# LinuxBoard_v1_4.net
KiCad netlist of a schematic drawn in EAGLE
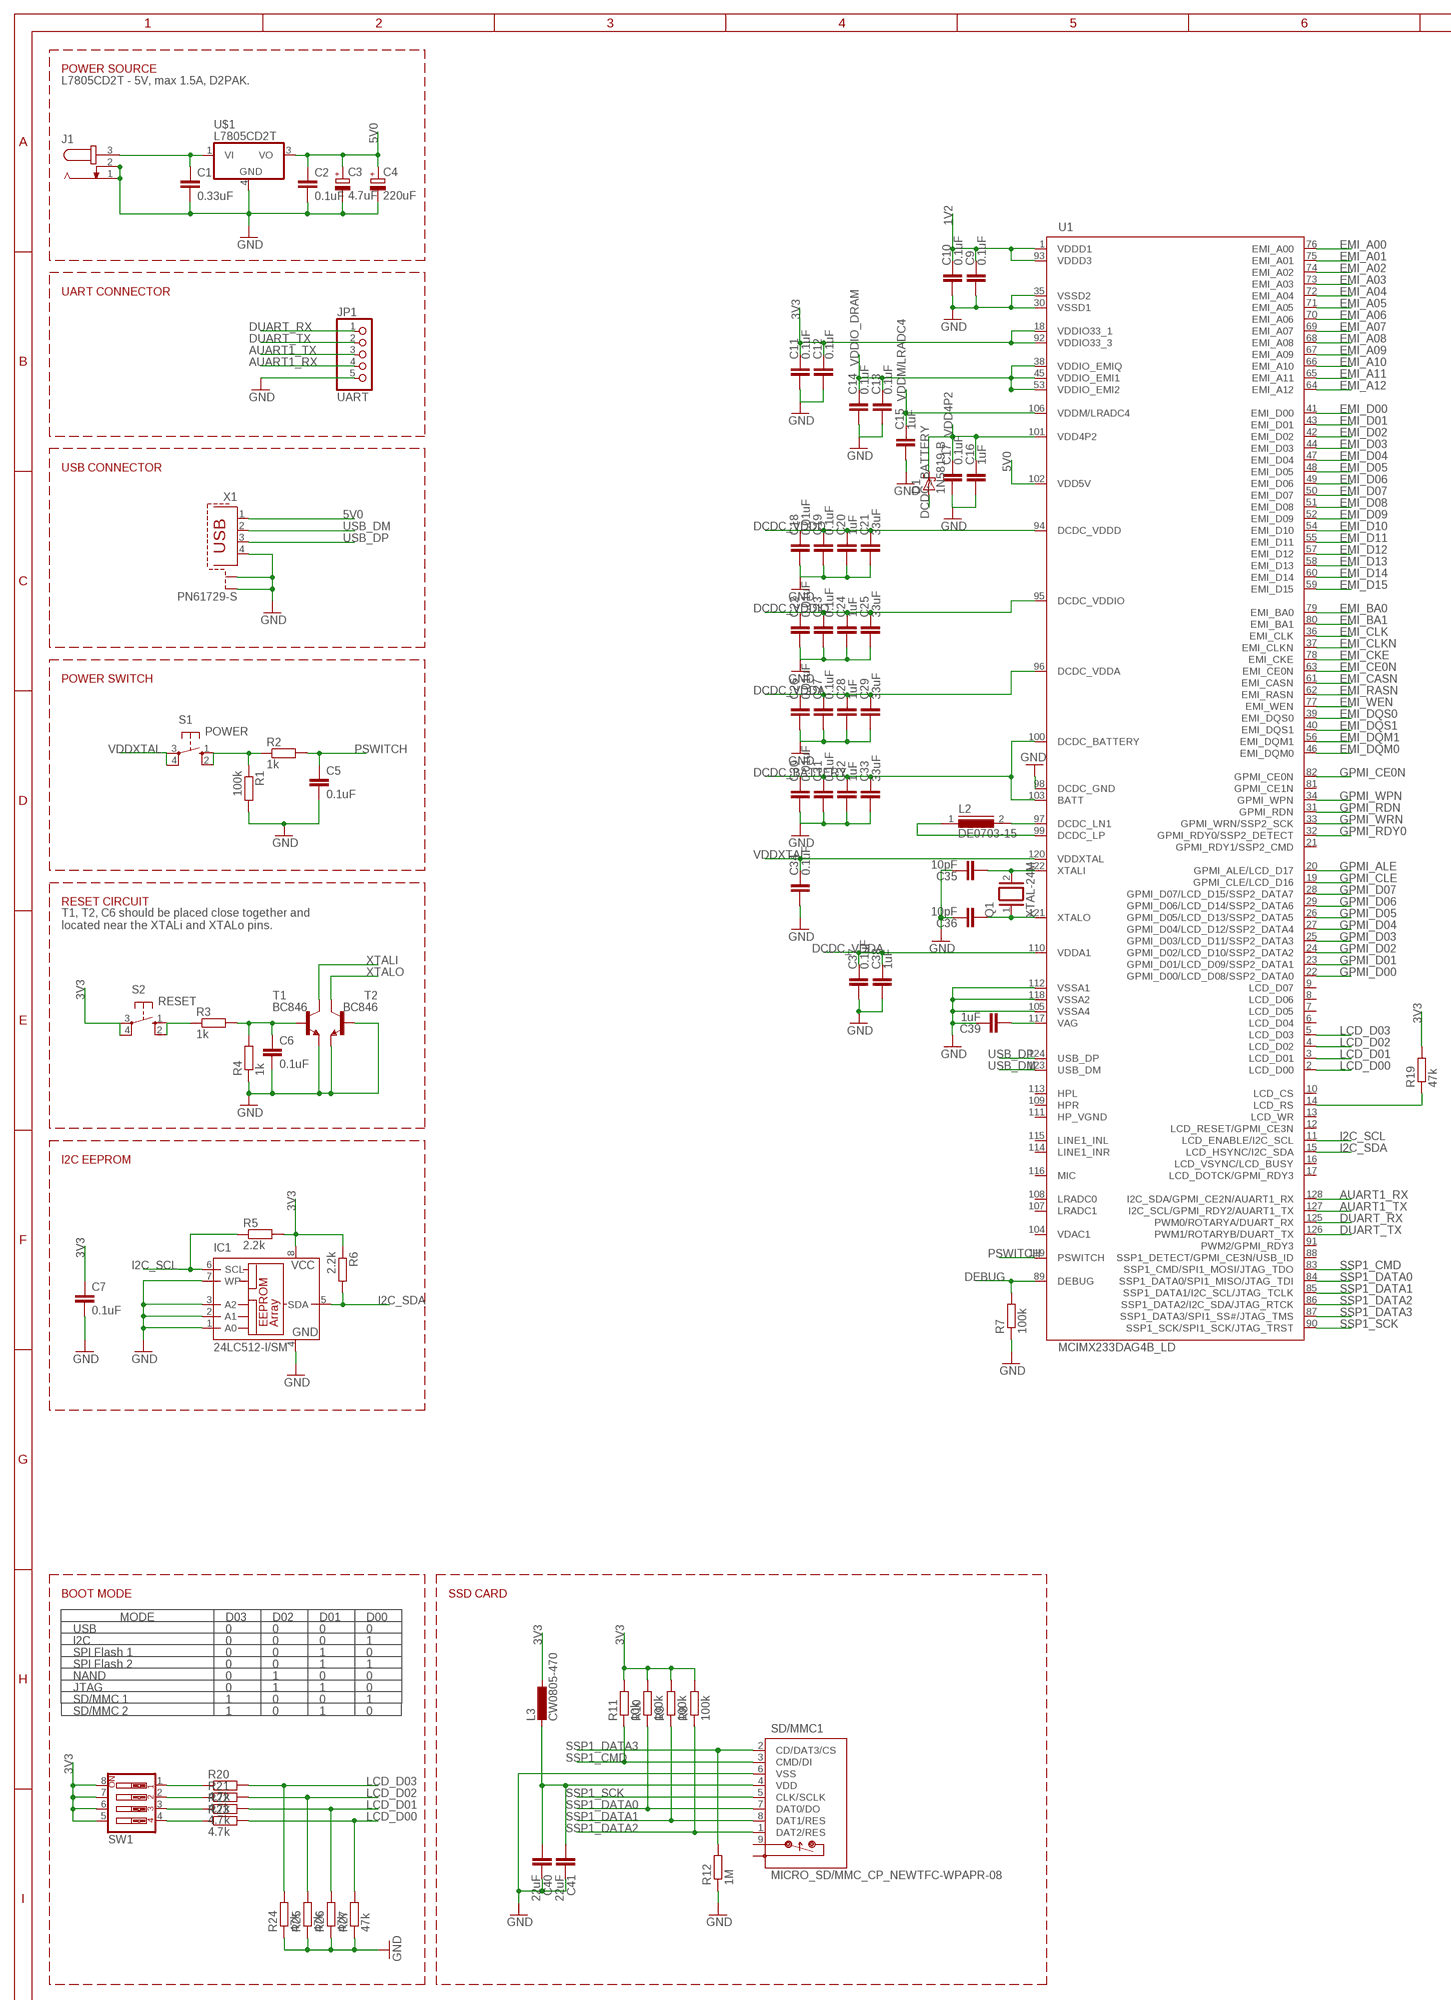
[diagram p0: schematic, sheet 1, part 1 of 2]
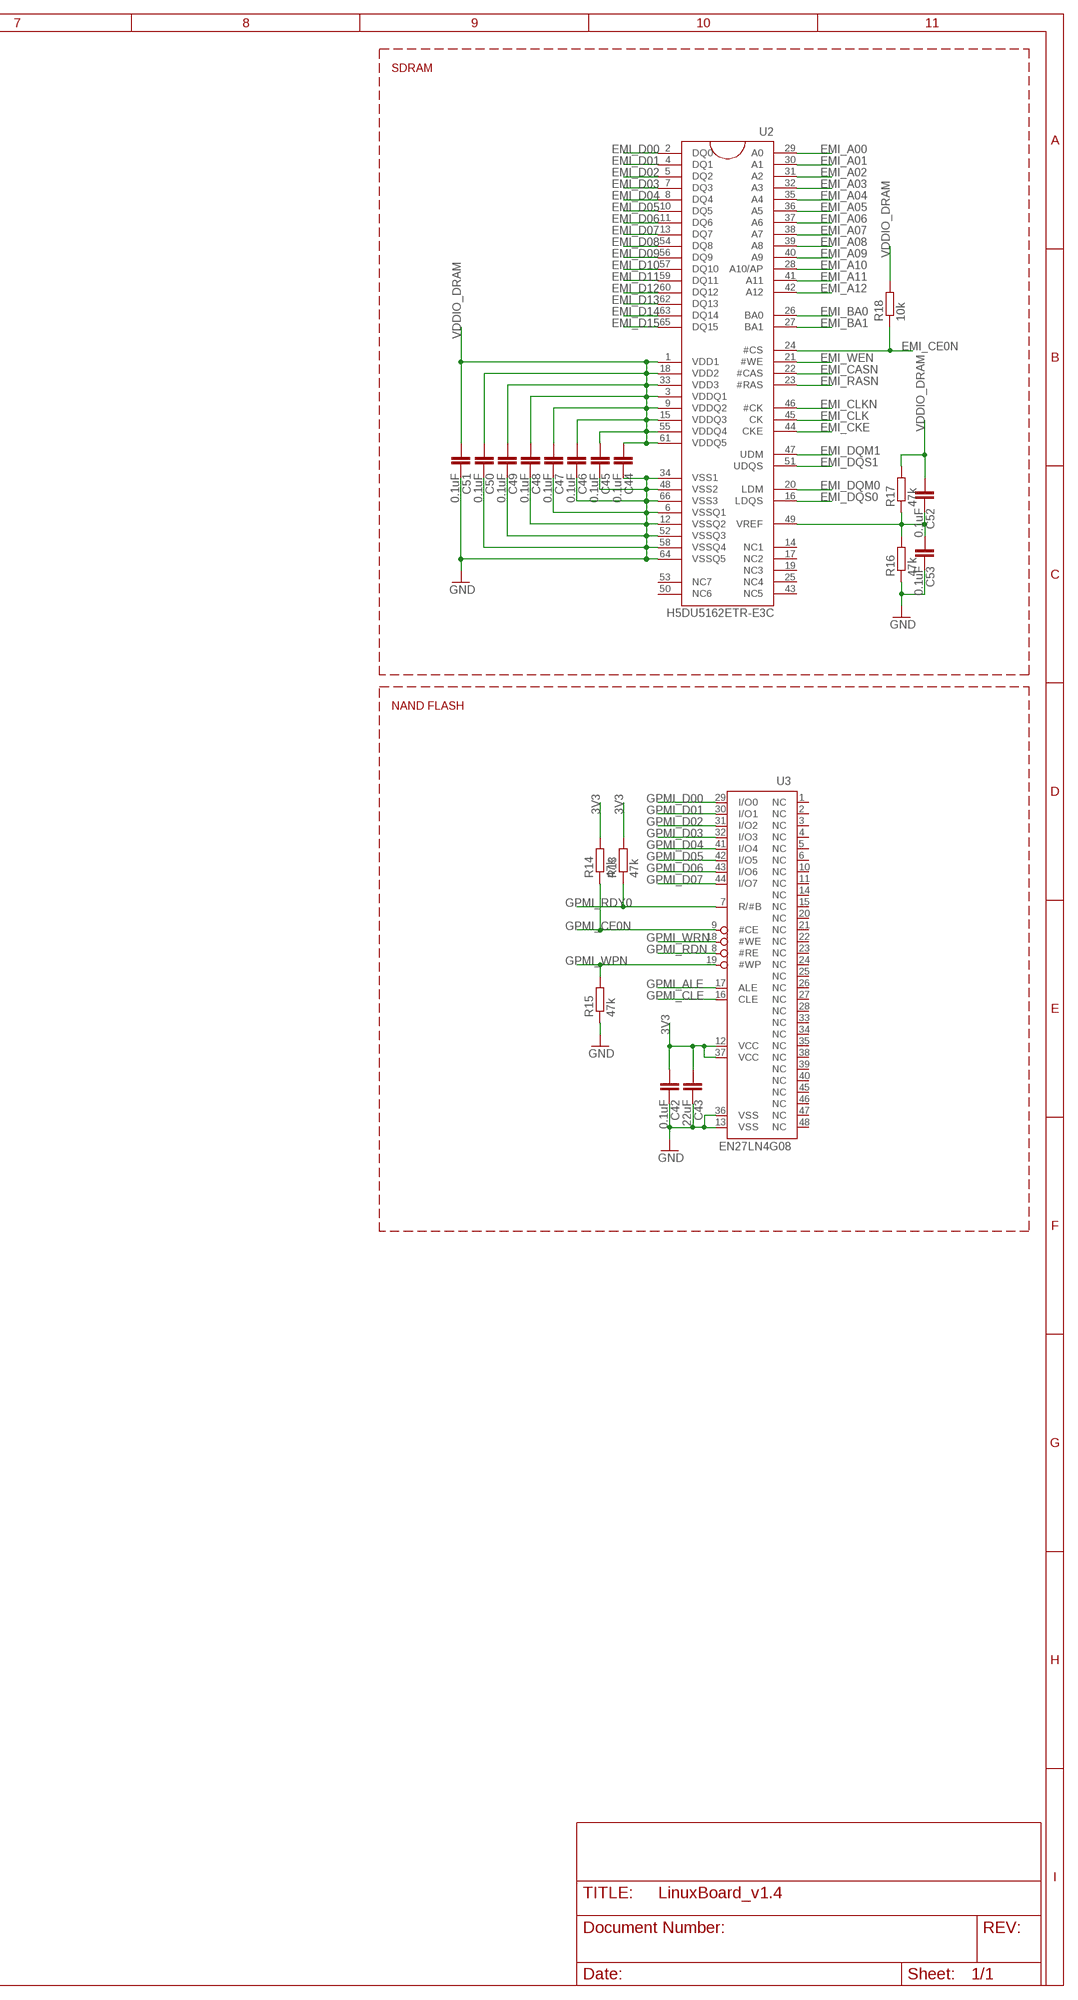
[diagram p1: schematic, sheet 1, part 2 of 2]

(export (version "E")
  (design (tool "Eeschema 10.0.6"))
  (components
    (comp (ref "C1")
      (value "0.33uF")
      (footprint "eagle-import:C0805")
      (libsource (lib "eagle-import") (part "C-EUC0805"))
    )
    (comp (ref "C2")
      (value "0.1uF")
      (footprint "eagle-import:C0805")
      (libsource (lib "eagle-import") (part "C-EUC0805"))
    )
    (comp (ref "C3")
      (value "4.7uF")
      (footprint "eagle-import:E2-5")
      (libsource (lib "eagle-import") (part "CPOL-EUE2-5"))
    )
    (comp (ref "C4")
      (value "220uF")
      (footprint "eagle-import:E2-5")
      (libsource (lib "eagle-import") (part "CPOL-EUE2-5"))
    )
    (comp (ref "C5")
      (value "0.1uF")
      (footprint "eagle-import:C0805")
      (libsource (lib "eagle-import") (part "C-EUC0805"))
    )
    (comp (ref "C6")
      (value "0.1uF")
      (footprint "eagle-import:C0805")
      (libsource (lib "eagle-import") (part "C-EUC0805"))
    )
    (comp (ref "C7")
      (value "0.1uF")
      (footprint "eagle-import:C0805")
      (libsource (lib "eagle-import") (part "C-EUC0805"))
    )
    (comp (ref "C9")
      (value "0.1uF")
      (footprint "eagle-import:C0805")
      (libsource (lib "eagle-import") (part "C-EUC0805"))
    )
    (comp (ref "C10")
      (value "0.1uF")
      (footprint "eagle-import:C0805")
      (libsource (lib "eagle-import") (part "C-EUC0805"))
    )
    (comp (ref "C11")
      (value "0.1uF")
      (footprint "eagle-import:C0805")
      (libsource (lib "eagle-import") (part "C-EUC0805"))
    )
    (comp (ref "C12")
      (value "0.1uF")
      (footprint "eagle-import:C0805")
      (libsource (lib "eagle-import") (part "C-EUC0805"))
    )
    (comp (ref "C13")
      (value "0.1uF")
      (footprint "eagle-import:C0805")
      (libsource (lib "eagle-import") (part "C-EUC0805"))
    )
    (comp (ref "C14")
      (value "0.1uF")
      (footprint "eagle-import:C0805")
      (libsource (lib "eagle-import") (part "C-EUC0805"))
    )
    (comp (ref "C15")
      (value "1uF")
      (footprint "eagle-import:C0805")
      (libsource (lib "eagle-import") (part "C-EUC0805"))
    )
    (comp (ref "C16")
      (value "1uF")
      (footprint "eagle-import:C0805")
      (libsource (lib "eagle-import") (part "C-EUC0805"))
    )
    (comp (ref "C17")
      (value "0.1uF")
      (footprint "eagle-import:C0805")
      (libsource (lib "eagle-import") (part "C-EUC0805"))
    )
    (comp (ref "C18")
      (value "0.01uF")
      (footprint "eagle-import:C0805")
      (libsource (lib "eagle-import") (part "C-EUC0805"))
    )
    (comp (ref "C19")
      (value "0.1uF")
      (footprint "eagle-import:C0805")
      (libsource (lib "eagle-import") (part "C-EUC0805"))
    )
    (comp (ref "C20")
      (value "1uF")
      (footprint "eagle-import:C0805")
      (libsource (lib "eagle-import") (part "C-EUC0805"))
    )
    (comp (ref "C21")
      (value "33uF")
      (footprint "eagle-import:C0805")
      (libsource (lib "eagle-import") (part "C-EUC0805"))
    )
    (comp (ref "C22")
      (value "0.01uF")
      (footprint "eagle-import:C0805")
      (libsource (lib "eagle-import") (part "C-EUC0805"))
    )
    (comp (ref "C23")
      (value "0.1uF")
      (footprint "eagle-import:C0805")
      (libsource (lib "eagle-import") (part "C-EUC0805"))
    )
    (comp (ref "C24")
      (value "1uF")
      (footprint "eagle-import:C0805")
      (libsource (lib "eagle-import") (part "C-EUC0805"))
    )
    (comp (ref "C25")
      (value "33uF")
      (footprint "eagle-import:C0805")
      (libsource (lib "eagle-import") (part "C-EUC0805"))
    )
    (comp (ref "C26")
      (value "0.01uF")
      (footprint "eagle-import:C0805")
      (libsource (lib "eagle-import") (part "C-EUC0805"))
    )
    (comp (ref "C27")
      (value "0.1uF")
      (footprint "eagle-import:C0805")
      (libsource (lib "eagle-import") (part "C-EUC0805"))
    )
    (comp (ref "C28")
      (value "1uF")
      (footprint "eagle-import:C0805")
      (libsource (lib "eagle-import") (part "C-EUC0805"))
    )
    (comp (ref "C29")
      (value "33uF")
      (footprint "eagle-import:C0805")
      (libsource (lib "eagle-import") (part "C-EUC0805"))
    )
    (comp (ref "C30")
      (value "0.01uF")
      (footprint "eagle-import:C0805")
      (libsource (lib "eagle-import") (part "C-EUC0805"))
    )
    (comp (ref "C31")
      (value "0.1uF")
      (footprint "eagle-import:C0805")
      (libsource (lib "eagle-import") (part "C-EUC0805"))
    )
    (comp (ref "C32")
      (value "1uF")
      (footprint "eagle-import:C0805")
      (libsource (lib "eagle-import") (part "C-EUC0805"))
    )
    (comp (ref "C33")
      (value "33uF")
      (footprint "eagle-import:C0805")
      (libsource (lib "eagle-import") (part "C-EUC0805"))
    )
    (comp (ref "C34")
      (value "0.1uF")
      (footprint "eagle-import:C0805")
      (libsource (lib "eagle-import") (part "C-EUC0805"))
    )
    (comp (ref "C35")
      (value "10pF")
      (footprint "eagle-import:C0805")
      (libsource (lib "eagle-import") (part "C-EUC0805"))
    )
    (comp (ref "C36")
      (value "10pF")
      (footprint "eagle-import:C0805")
      (libsource (lib "eagle-import") (part "C-EUC0805"))
    )
    (comp (ref "C37")
      (value "0.1uF")
      (footprint "eagle-import:C0805")
      (libsource (lib "eagle-import") (part "C-EUC0805"))
    )
    (comp (ref "C38")
      (value "1uF")
      (footprint "eagle-import:C0805")
      (libsource (lib "eagle-import") (part "C-EUC0805"))
    )
    (comp (ref "C39")
      (value "1uF")
      (footprint "eagle-import:C0805")
      (libsource (lib "eagle-import") (part "C-EUC0805"))
    )
    (comp (ref "C40")
      (value "22uF")
      (footprint "eagle-import:C0805")
      (libsource (lib "eagle-import") (part "C-EUC0805"))
    )
    (comp (ref "C41")
      (value "22uF")
      (footprint "eagle-import:C0805")
      (libsource (lib "eagle-import") (part "C-EUC0805"))
    )
    (comp (ref "C42")
      (value "0.1uF")
      (footprint "eagle-import:C0805")
      (libsource (lib "eagle-import") (part "C-EUC0805"))
    )
    (comp (ref "C43")
      (value "22uF")
      (footprint "eagle-import:C0805")
      (libsource (lib "eagle-import") (part "C-EUC0805"))
    )
    (comp (ref "C44")
      (value "0.1uF")
      (footprint "eagle-import:C0805")
      (libsource (lib "eagle-import") (part "C-EUC0805"))
    )
    (comp (ref "C45")
      (value "0.1uF")
      (footprint "eagle-import:C0805")
      (libsource (lib "eagle-import") (part "C-EUC0805"))
    )
    (comp (ref "C46")
      (value "0.1uF")
      (footprint "eagle-import:C0805")
      (libsource (lib "eagle-import") (part "C-EUC0805"))
    )
    (comp (ref "C47")
      (value "0.1uF")
      (footprint "eagle-import:C0805")
      (libsource (lib "eagle-import") (part "C-EUC0805"))
    )
    (comp (ref "C48")
      (value "0.1uF")
      (footprint "eagle-import:C0805")
      (libsource (lib "eagle-import") (part "C-EUC0805"))
    )
    (comp (ref "C49")
      (value "0.1uF")
      (footprint "eagle-import:C0805")
      (libsource (lib "eagle-import") (part "C-EUC0805"))
    )
    (comp (ref "C50")
      (value "0.1uF")
      (footprint "eagle-import:C0805")
      (libsource (lib "eagle-import") (part "C-EUC0805"))
    )
    (comp (ref "C51")
      (value "0.1uF")
      (footprint "eagle-import:C0805")
      (libsource (lib "eagle-import") (part "C-EUC0805"))
    )
    (comp (ref "C52")
      (value "0.1uF")
      (footprint "eagle-import:C0805")
      (libsource (lib "eagle-import") (part "C-EUC0805"))
    )
    (comp (ref "C53")
      (value "0.1uF")
      (footprint "eagle-import:C0805")
      (libsource (lib "eagle-import") (part "C-EUC0805"))
    )
    (comp (ref "D1")
      (value "1N5819-B")
      (footprint "eagle-import:DO41-7.6")
      (libsource (lib "eagle-import") (part "1N5819-B"))
    )
    (comp (ref "IC1")
      (value "24LC512-I/SM")
      (footprint "eagle-import:SO-08")
      (fields (field (name "MF") "MICROCHIP") (field (name "MPN") "24LC128-I/SNG"))
      (libsource (lib "eagle-import") (part "24SNLC128"))
    )
    (comp (ref "J1")
      (value "JACK-PLUG0")
      (footprint "eagle-import:SPC4077")
      (libsource (lib "eagle-import") (part "JACK-PLUG0"))
    )
    (comp (ref "JP1")
      (value "UART")
      (footprint "eagle-import:1X05")
      (libsource (lib "eagle-import") (part "PINHD-1X5"))
    )
    (comp (ref "L2")
      (value "DE0703-15")
      (footprint "eagle-import:DR73")
      (libsource (lib "eagle-import") (part "DR73"))
    )
    (comp (ref "L3")
      (value "CW0805-470")
      (footprint "eagle-import:L2012C")
      (libsource (lib "eagle-import") (part "L-EUL2012C"))
    )
    (comp (ref "Q1")
      (value "XTAL-24M")
      (footprint "eagle-import:QS")
      (libsource (lib "eagle-import") (part "XTAL/S"))
    )
    (comp (ref "R1")
      (value "100k")
      (footprint "eagle-import:R0805")
      (libsource (lib "eagle-import") (part "R-EU_R0805"))
    )
    (comp (ref "R2")
      (value "1k")
      (footprint "eagle-import:R0805")
      (libsource (lib "eagle-import") (part "R-EU_R0805"))
    )
    (comp (ref "R3")
      (value "1k")
      (footprint "eagle-import:R0805")
      (libsource (lib "eagle-import") (part "R-EU_R0805"))
    )
    (comp (ref "R4")
      (value "1k")
      (footprint "eagle-import:R0805")
      (libsource (lib "eagle-import") (part "R-EU_R0805"))
    )
    (comp (ref "R5")
      (value "2.2k")
      (footprint "eagle-import:R0805")
      (libsource (lib "eagle-import") (part "R-EU_R0805"))
    )
    (comp (ref "R6")
      (value "2.2k")
      (footprint "eagle-import:R0805")
      (libsource (lib "eagle-import") (part "R-EU_R0805"))
    )
    (comp (ref "R7")
      (value "100k")
      (footprint "eagle-import:R0805")
      (libsource (lib "eagle-import") (part "R-EU_R0805"))
    )
    (comp (ref "R8")
      (value "100k")
      (footprint "eagle-import:R0805")
      (libsource (lib "eagle-import") (part "R-EU_R0805"))
    )
    (comp (ref "R9")
      (value "100k")
      (footprint "eagle-import:R0805")
      (libsource (lib "eagle-import") (part "R-EU_R0805"))
    )
    (comp (ref "R10")
      (value "100k")
      (footprint "eagle-import:R0805")
      (libsource (lib "eagle-import") (part "R-EU_R0805"))
    )
    (comp (ref "R11")
      (value "10k")
      (footprint "eagle-import:R0805")
      (libsource (lib "eagle-import") (part "R-EU_R0805"))
    )
    (comp (ref "R12")
      (value "1M")
      (footprint "eagle-import:R0805")
      (libsource (lib "eagle-import") (part "R-EU_R0805"))
    )
    (comp (ref "R13")
      (value "47k")
      (footprint "eagle-import:R0805")
      (libsource (lib "eagle-import") (part "R-EU_R0805"))
    )
    (comp (ref "R14")
      (value "47k")
      (footprint "eagle-import:R0805")
      (libsource (lib "eagle-import") (part "R-EU_R0805"))
    )
    (comp (ref "R15")
      (value "47k")
      (footprint "eagle-import:R0805")
      (libsource (lib "eagle-import") (part "R-EU_R0805"))
    )
    (comp (ref "R16")
      (value "47k")
      (footprint "eagle-import:R0805")
      (libsource (lib "eagle-import") (part "R-EU_R0805"))
    )
    (comp (ref "R17")
      (value "47k")
      (footprint "eagle-import:R0805")
      (libsource (lib "eagle-import") (part "R-EU_R0805"))
    )
    (comp (ref "R18")
      (value "10k")
      (footprint "eagle-import:R0805")
      (libsource (lib "eagle-import") (part "R-EU_R0805"))
    )
    (comp (ref "R19")
      (value "47k")
      (footprint "eagle-import:R0805")
      (libsource (lib "eagle-import") (part "R-EU_R0805"))
    )
    (comp (ref "R20")
      (value "4.7k")
      (footprint "eagle-import:R0805")
      (libsource (lib "eagle-import") (part "R-EU_R0805"))
    )
    (comp (ref "R21")
      (value "4.7k")
      (footprint "eagle-import:R0805")
      (libsource (lib "eagle-import") (part "R-EU_R0805"))
    )
    (comp (ref "R22")
      (value "4.7k")
      (footprint "eagle-import:R0805")
      (libsource (lib "eagle-import") (part "R-EU_R0805"))
    )
    (comp (ref "R23")
      (value "4.7k")
      (footprint "eagle-import:R0805")
      (libsource (lib "eagle-import") (part "R-EU_R0805"))
    )
    (comp (ref "R24")
      (value "47k")
      (footprint "eagle-import:R0805")
      (libsource (lib "eagle-import") (part "R-EU_R0805"))
    )
    (comp (ref "R25")
      (value "47k")
      (footprint "eagle-import:R0805")
      (libsource (lib "eagle-import") (part "R-EU_R0805"))
    )
    (comp (ref "R26")
      (value "47k")
      (footprint "eagle-import:R0805")
      (libsource (lib "eagle-import") (part "R-EU_R0805"))
    )
    (comp (ref "R27")
      (value "47k")
      (footprint "eagle-import:R0805")
      (libsource (lib "eagle-import") (part "R-EU_R0805"))
    )
    (comp (ref "S1")
      (value "POWER")
      (footprint "eagle-import:B3F-10XX")
      (fields (field (name "MPN") "B3F-1000"))
      (libsource (lib "eagle-import") (part "10-XX"))
    )
    (comp (ref "S2")
      (value "RESET")
      (footprint "eagle-import:B3F-10XX")
      (fields (field (name "MPN") "B3F-1000"))
      (libsource (lib "eagle-import") (part "10-XX"))
    )
    (comp (ref "SD/MMC1")
      (value "MICRO_SD/MMC_CP_NEWTFC-WPAPR-08")
      (footprint "eagle-import:TFC-WPAPR-08")
      (libsource (lib "eagle-import") (part "MICRO_SD/MMC_CP_NEWTFC-WPAPR-08"))
    )
    (comp (ref "SW1")
      (value "SW_DIP-4")
      (footprint "eagle-import:EDG-04")
      (libsource (lib "eagle-import") (part "SW_DIP-4"))
    )
    (comp (ref "T1")
      (value "BC846")
      (footprint "eagle-import:SOT23")
      (libsource (lib "eagle-import") (part "BC846"))
    )
    (comp (ref "T2")
      (value "BC846")
      (footprint "eagle-import:SOT23")
      (libsource (lib "eagle-import") (part "BC846"))
    )
    (comp (ref "U$1")
      (value "L7805CD2T")
      (footprint "eagle-import:D2PAK-3")
      (libsource (lib "eagle-import") (part "L7805CD2T"))
    )
    (comp (ref "U1")
      (value "MCIMX233DAG4B_LD")
      (footprint "eagle-import:TQFP128LD")
      (libsource (lib "eagle-import") (part "MCIMX233DAG4B_LD"))
    )
    (comp (ref "U2")
      (value "H5DU5162ETR-E3C")
      (footprint "eagle-import:66TSOP-II")
      (libsource (lib "eagle-import") (part "HY5DU121622D(L)T(P)-J"))
    )
    (comp (ref "U3")
      (value "EN27LN4G08")
      (footprint "eagle-import:TSOP48")
      (libsource (lib "eagle-import") (part "H27UBG8T2A"))
    )
    (comp (ref "X1")
      (value "PN61729-S")
      (footprint "eagle-import:PN61729-S")
      (libsource (lib "eagle-import") (part "PN61729-S"))
    )
  )
  (nets
    (net (code "1") (name "/1V2") (class "Default")
      (node (ref "C10") (pin "1") (pinfunction "1_1") (pintype "passive"))
      (node (ref "C9") (pin "1") (pinfunction "1_1") (pintype "passive"))
      (node (ref "U1") (pin "1") (pinfunction "VDDD1_1") (pintype "power_in"))
      (node (ref "U1") (pin "93") (pinfunction "VDDD3_93") (pintype "power_in"))
    )
    (net (code "2") (name "/3V3") (class "Default")
      (node (ref "C11") (pin "1") (pinfunction "1_1") (pintype "passive"))
      (node (ref "C12") (pin "1") (pinfunction "1_1") (pintype "passive"))
      (node (ref "C42") (pin "2") (pinfunction "2_2") (pintype "passive"))
      (node (ref "C43") (pin "2") (pinfunction "2_2") (pintype "passive"))
      (node (ref "C7") (pin "1") (pinfunction "1_1") (pintype "passive"))
      (node (ref "IC1") (pin "8") (pinfunction "VCC_8") (pintype "power_in"))
      (node (ref "L3") (pin "1") (pinfunction "1_1") (pintype "passive"))
      (node (ref "R10") (pin "2") (pinfunction "2_2") (pintype "passive"))
      (node (ref "R11") (pin "2") (pinfunction "2_2") (pintype "passive"))
      (node (ref "R13") (pin "2") (pinfunction "2_2") (pintype "passive"))
      (node (ref "R14") (pin "2") (pinfunction "2_2") (pintype "passive"))
      (node (ref "R19") (pin "2") (pinfunction "2_2") (pintype "passive"))
      (node (ref "R5") (pin "2") (pinfunction "2_2") (pintype "passive"))
      (node (ref "R6") (pin "1") (pinfunction "1_1") (pintype "passive"))
      (node (ref "R8") (pin "2") (pinfunction "2_2") (pintype "passive"))
      (node (ref "R9") (pin "2") (pinfunction "2_2") (pintype "passive"))
      (node (ref "S2") (pin "3") (pinfunction "P_3") (pintype "passive"))
      (node (ref "S2") (pin "4") (pinfunction "P1_4") (pintype "passive"))
      (node (ref "SW1") (pin "5") (pinfunction "5_5") (pintype "passive"))
      (node (ref "SW1") (pin "6") (pinfunction "6_6") (pintype "passive"))
      (node (ref "SW1") (pin "7") (pinfunction "7_7") (pintype "passive"))
      (node (ref "SW1") (pin "8") (pinfunction "8_8") (pintype "passive"))
      (node (ref "U1") (pin "18") (pinfunction "VDDIO33_1_18") (pintype "power_in"))
      (node (ref "U1") (pin "92") (pinfunction "VDDIO33_3_92") (pintype "power_in"))
      (node (ref "U3") (pin "12") (pinfunction "VCC_12") (pintype "power_in"))
      (node (ref "U3") (pin "37") (pinfunction "VCC_37") (pintype "power_in"))
    )
    (net (code "3") (name "/5V0") (class "Default")
      (node (ref "C2") (pin "1") (pinfunction "1_1") (pintype "passive"))
      (node (ref "C3") (pin "+") (pinfunction "+_+") (pintype "passive"))
      (node (ref "C4") (pin "+") (pinfunction "+_+") (pintype "passive"))
      (node (ref "U$1") (pin "3") (pinfunction "VO_3") (pintype "passive"))
      (node (ref "U1") (pin "102") (pinfunction "VDD5V_102") (pintype "power_in"))
      (node (ref "X1") (pin "1") (pinfunction "1_1") (pintype "passive"))
    )
    (net (code "4") (name "/AUART1_RX") (class "Default")
      (node (ref "JP1") (pin "4") (pinfunction "4_4") (pintype "passive"))
      (node (ref "U1") (pin "128") (pinfunction "I2C_SDA/GPMI_CE2N/AUART1_RX_128") (pintype "bidirectional"))
    )
    (net (code "5") (name "/AUART1_TX") (class "Default")
      (node (ref "JP1") (pin "3") (pinfunction "3_3") (pintype "passive"))
      (node (ref "U1") (pin "127") (pinfunction "I2C_SCL/GPMI_RDY2/AUART1_TX_127") (pintype "bidirectional"))
    )
    (net (code "6") (name "/DCDC_BATTERY") (class "Default")
      (node (ref "C30") (pin "1") (pinfunction "1_1") (pintype "passive"))
      (node (ref "C31") (pin "1") (pinfunction "1_1") (pintype "passive"))
      (node (ref "C32") (pin "1") (pinfunction "1_1") (pintype "passive"))
      (node (ref "C33") (pin "1") (pinfunction "1_1") (pintype "passive"))
      (node (ref "D1") (pin "A") (pinfunction "A_A") (pintype "passive"))
      (node (ref "U1") (pin "100") (pinfunction "DCDC_BATTERY_100") (pintype "power_in"))
      (node (ref "U1") (pin "103") (pinfunction "BATT_103") (pintype "input"))
    )
    (net (code "7") (name "/DCDC_VDDA") (class "Default")
      (node (ref "C26") (pin "1") (pinfunction "1_1") (pintype "passive"))
      (node (ref "C27") (pin "1") (pinfunction "1_1") (pintype "passive"))
      (node (ref "C28") (pin "1") (pinfunction "1_1") (pintype "passive"))
      (node (ref "C29") (pin "1") (pinfunction "1_1") (pintype "passive"))
      (node (ref "C37") (pin "1") (pinfunction "1_1") (pintype "passive"))
      (node (ref "C38") (pin "1") (pinfunction "1_1") (pintype "passive"))
      (node (ref "U1") (pin "110") (pinfunction "VDDA1_110") (pintype "power_in"))
      (node (ref "U1") (pin "96") (pinfunction "DCDC_VDDA_96") (pintype "power_in"))
    )
    (net (code "8") (name "/DCDC_VDDD") (class "Default")
      (node (ref "C18") (pin "1") (pinfunction "1_1") (pintype "passive"))
      (node (ref "C19") (pin "1") (pinfunction "1_1") (pintype "passive"))
      (node (ref "C20") (pin "1") (pinfunction "1_1") (pintype "passive"))
      (node (ref "C21") (pin "1") (pinfunction "1_1") (pintype "passive"))
      (node (ref "U1") (pin "94") (pinfunction "DCDC_VDDD_94") (pintype "power_in"))
    )
    (net (code "9") (name "/DCDC_VDDIO") (class "Default")
      (node (ref "C22") (pin "1") (pinfunction "1_1") (pintype "passive"))
      (node (ref "C23") (pin "1") (pinfunction "1_1") (pintype "passive"))
      (node (ref "C24") (pin "1") (pinfunction "1_1") (pintype "passive"))
      (node (ref "C25") (pin "1") (pinfunction "1_1") (pintype "passive"))
      (node (ref "U1") (pin "95") (pinfunction "DCDC_VDDIO_95") (pintype "power_in"))
    )
    (net (code "10") (name "/DEBUG") (class "Default")
      (node (ref "R7") (pin "2") (pinfunction "2_2") (pintype "passive"))
      (node (ref "U1") (pin "89") (pinfunction "DEBUG_89") (pintype "bidirectional"))
    )
    (net (code "11") (name "/DUART_RX") (class "Default")
      (node (ref "JP1") (pin "1") (pinfunction "1_1") (pintype "passive"))
      (node (ref "U1") (pin "125") (pinfunction "PWM0/ROTARYA/DUART_RX_125") (pintype "bidirectional"))
    )
    (net (code "12") (name "/DUART_TX") (class "Default")
      (node (ref "JP1") (pin "2") (pinfunction "2_2") (pintype "passive"))
      (node (ref "U1") (pin "126") (pinfunction "PWM1/ROTARYB/DUART_TX_126") (pintype "bidirectional"))
    )
    (net (code "13") (name "/EMI_A00") (class "Default")
      (node (ref "U1") (pin "76") (pinfunction "EMI_A00_76") (pintype "bidirectional"))
      (node (ref "U2") (pin "29") (pinfunction "A0_29") (pintype "input"))
    )
    (net (code "14") (name "/EMI_A01") (class "Default")
      (node (ref "U1") (pin "75") (pinfunction "EMI_A01_75") (pintype "bidirectional"))
      (node (ref "U2") (pin "30") (pinfunction "A1_30") (pintype "input"))
    )
    (net (code "15") (name "/EMI_A02") (class "Default")
      (node (ref "U1") (pin "74") (pinfunction "EMI_A02_74") (pintype "bidirectional"))
      (node (ref "U2") (pin "31") (pinfunction "A2_31") (pintype "input"))
    )
    (net (code "16") (name "/EMI_A03") (class "Default")
      (node (ref "U1") (pin "73") (pinfunction "EMI_A03_73") (pintype "bidirectional"))
      (node (ref "U2") (pin "32") (pinfunction "A3_32") (pintype "input"))
    )
    (net (code "17") (name "/EMI_A04") (class "Default")
      (node (ref "U1") (pin "72") (pinfunction "EMI_A04_72") (pintype "bidirectional"))
      (node (ref "U2") (pin "35") (pinfunction "A4_35") (pintype "input"))
    )
    (net (code "18") (name "/EMI_A05") (class "Default")
      (node (ref "U1") (pin "71") (pinfunction "EMI_A05_71") (pintype "bidirectional"))
      (node (ref "U2") (pin "36") (pinfunction "A5_36") (pintype "input"))
    )
    (net (code "19") (name "/EMI_A06") (class "Default")
      (node (ref "U1") (pin "70") (pinfunction "EMI_A06_70") (pintype "bidirectional"))
      (node (ref "U2") (pin "37") (pinfunction "A6_37") (pintype "input"))
    )
    (net (code "20") (name "/EMI_A07") (class "Default")
      (node (ref "U1") (pin "69") (pinfunction "EMI_A07_69") (pintype "bidirectional"))
      (node (ref "U2") (pin "38") (pinfunction "A7_38") (pintype "input"))
    )
    (net (code "21") (name "/EMI_A08") (class "Default")
      (node (ref "U1") (pin "68") (pinfunction "EMI_A08_68") (pintype "bidirectional"))
      (node (ref "U2") (pin "39") (pinfunction "A8_39") (pintype "input"))
    )
    (net (code "22") (name "/EMI_A09") (class "Default")
      (node (ref "U1") (pin "67") (pinfunction "EMI_A09_67") (pintype "bidirectional"))
      (node (ref "U2") (pin "40") (pinfunction "A9_40") (pintype "input"))
    )
    (net (code "23") (name "/EMI_A10") (class "Default")
      (node (ref "U1") (pin "66") (pinfunction "EMI_A10_66") (pintype "bidirectional"))
      (node (ref "U2") (pin "28") (pinfunction "A10/AP_28") (pintype "input"))
    )
    (net (code "24") (name "/EMI_A11") (class "Default")
      (node (ref "U1") (pin "65") (pinfunction "EMI_A11_65") (pintype "bidirectional"))
      (node (ref "U2") (pin "41") (pinfunction "A11_41") (pintype "input"))
    )
    (net (code "25") (name "/EMI_A12") (class "Default")
      (node (ref "U1") (pin "64") (pinfunction "EMI_A12_64") (pintype "bidirectional"))
      (node (ref "U2") (pin "42") (pinfunction "A12_42") (pintype "input"))
    )
    (net (code "26") (name "/EMI_BA0") (class "Default")
      (node (ref "U1") (pin "79") (pinfunction "EMI_BA0_79") (pintype "output"))
      (node (ref "U2") (pin "26") (pinfunction "BA0_26") (pintype "input"))
    )
    (net (code "27") (name "/EMI_BA1") (class "Default")
      (node (ref "U1") (pin "80") (pinfunction "EMI_BA1_80") (pintype "output"))
      (node (ref "U2") (pin "27") (pinfunction "BA1_27") (pintype "input"))
    )
    (net (code "28") (name "/EMI_CASN") (class "Default")
      (node (ref "U1") (pin "61") (pinfunction "EMI_CASN_61") (pintype "output"))
      (node (ref "U2") (pin "22") (pinfunction "#CAS_22") (pintype "input"))
    )
    (net (code "29") (name "/EMI_CE0N") (class "Default")
      (node (ref "R18") (pin "1") (pinfunction "1_1") (pintype "passive"))
      (node (ref "U1") (pin "63") (pinfunction "EMI_CE0N_63") (pintype "output"))
      (node (ref "U2") (pin "24") (pinfunction "#CS_24") (pintype "input"))
    )
    (net (code "30") (name "/EMI_CKE") (class "Default")
      (node (ref "U1") (pin "78") (pinfunction "EMI_CKE_78") (pintype "output"))
      (node (ref "U2") (pin "44") (pinfunction "CKE_44") (pintype "input"))
    )
    (net (code "31") (name "/EMI_CLK") (class "Default")
      (node (ref "U1") (pin "36") (pinfunction "EMI_CLK_36") (pintype "output"))
      (node (ref "U2") (pin "45") (pinfunction "CK_45") (pintype "input"))
    )
    (net (code "32") (name "/EMI_CLKN") (class "Default")
      (node (ref "U1") (pin "37") (pinfunction "EMI_CLKN_37") (pintype "output"))
      (node (ref "U2") (pin "46") (pinfunction "#CK_46") (pintype "input"))
    )
    (net (code "33") (name "/EMI_D00") (class "Default")
      (node (ref "U1") (pin "41") (pinfunction "EMI_D00_41") (pintype "bidirectional"))
      (node (ref "U2") (pin "2") (pinfunction "DQ0_2") (pintype "bidirectional"))
    )
    (net (code "34") (name "/EMI_D01") (class "Default")
      (node (ref "U1") (pin "43") (pinfunction "EMI_D01_43") (pintype "bidirectional"))
      (node (ref "U2") (pin "4") (pinfunction "DQ1_4") (pintype "bidirectional"))
    )
    (net (code "35") (name "/EMI_D02") (class "Default")
      (node (ref "U1") (pin "42") (pinfunction "EMI_D02_42") (pintype "bidirectional"))
      (node (ref "U2") (pin "5") (pinfunction "DQ2_5") (pintype "bidirectional"))
    )
    (net (code "36") (name "/EMI_D03") (class "Default")
      (node (ref "U1") (pin "44") (pinfunction "EMI_D03_44") (pintype "bidirectional"))
      (node (ref "U2") (pin "7") (pinfunction "DQ3_7") (pintype "bidirectional"))
    )
    (net (code "37") (name "/EMI_D04") (class "Default")
      (node (ref "U1") (pin "47") (pinfunction "EMI_D04_47") (pintype "bidirectional"))
      (node (ref "U2") (pin "8") (pinfunction "DQ4_8") (pintype "bidirectional"))
    )
    (net (code "38") (name "/EMI_D05") (class "Default")
      (node (ref "U1") (pin "48") (pinfunction "EMI_D05_48") (pintype "bidirectional"))
      (node (ref "U2") (pin "10") (pinfunction "DQ5_10") (pintype "bidirectional"))
    )
    (net (code "39") (name "/EMI_D06") (class "Default")
      (node (ref "U1") (pin "49") (pinfunction "EMI_D06_49") (pintype "bidirectional"))
      (node (ref "U2") (pin "11") (pinfunction "DQ6_11") (pintype "bidirectional"))
    )
    (net (code "40") (name "/EMI_D07") (class "Default")
      (node (ref "U1") (pin "50") (pinfunction "EMI_D07_50") (pintype "bidirectional"))
      (node (ref "U2") (pin "13") (pinfunction "DQ7_13") (pintype "bidirectional"))
    )
    (net (code "41") (name "/EMI_D08") (class "Default")
      (node (ref "U1") (pin "51") (pinfunction "EMI_D08_51") (pintype "bidirectional"))
      (node (ref "U2") (pin "54") (pinfunction "DQ8_54") (pintype "bidirectional"))
    )
    (net (code "42") (name "/EMI_D09") (class "Default")
      (node (ref "U1") (pin "52") (pinfunction "EMI_D09_52") (pintype "bidirectional"))
      (node (ref "U2") (pin "56") (pinfunction "DQ9_56") (pintype "bidirectional"))
    )
    (net (code "43") (name "/EMI_D10") (class "Default")
      (node (ref "U1") (pin "54") (pinfunction "EMI_D10_54") (pintype "bidirectional"))
      (node (ref "U2") (pin "57") (pinfunction "DQ10_57") (pintype "bidirectional"))
    )
    (net (code "44") (name "/EMI_D11") (class "Default")
      (node (ref "U1") (pin "55") (pinfunction "EMI_D11_55") (pintype "bidirectional"))
      (node (ref "U2") (pin "59") (pinfunction "DQ11_59") (pintype "bidirectional"))
    )
    (net (code "45") (name "/EMI_D12") (class "Default")
      (node (ref "U1") (pin "57") (pinfunction "EMI_D12_57") (pintype "bidirectional"))
      (node (ref "U2") (pin "60") (pinfunction "DQ12_60") (pintype "bidirectional"))
    )
    (net (code "46") (name "/EMI_D13") (class "Default")
      (node (ref "U1") (pin "58") (pinfunction "EMI_D13_58") (pintype "bidirectional"))
      (node (ref "U2") (pin "62") (pinfunction "DQ13_62") (pintype "bidirectional"))
    )
    (net (code "47") (name "/EMI_D14") (class "Default")
      (node (ref "U1") (pin "60") (pinfunction "EMI_D14_60") (pintype "bidirectional"))
      (node (ref "U2") (pin "63") (pinfunction "DQ14_63") (pintype "bidirectional"))
    )
    (net (code "48") (name "/EMI_D15") (class "Default")
      (node (ref "U1") (pin "59") (pinfunction "EMI_D15_59") (pintype "bidirectional"))
      (node (ref "U2") (pin "65") (pinfunction "DQ15_65") (pintype "bidirectional"))
    )
    (net (code "49") (name "/EMI_DQM0") (class "Default")
      (node (ref "U1") (pin "46") (pinfunction "EMI_DQM0_46") (pintype "output"))
      (node (ref "U2") (pin "20") (pinfunction "LDM_20") (pintype "input"))
    )
    (net (code "50") (name "/EMI_DQM1") (class "Default")
      (node (ref "U1") (pin "56") (pinfunction "EMI_DQM1_56") (pintype "output"))
      (node (ref "U2") (pin "47") (pinfunction "UDM_47") (pintype "input"))
    )
    (net (code "51") (name "/EMI_DQS0") (class "Default")
      (node (ref "U1") (pin "39") (pinfunction "EMI_DQS0_39") (pintype "output"))
      (node (ref "U2") (pin "16") (pinfunction "LDQS_16") (pintype "bidirectional"))
    )
    (net (code "52") (name "/EMI_DQS1") (class "Default")
      (node (ref "U1") (pin "40") (pinfunction "EMI_DQS1_40") (pintype "output"))
      (node (ref "U2") (pin "51") (pinfunction "UDQS_51") (pintype "input"))
    )
    (net (code "53") (name "/EMI_RASN") (class "Default")
      (node (ref "U1") (pin "62") (pinfunction "EMI_RASN_62") (pintype "output"))
      (node (ref "U2") (pin "23") (pinfunction "#RAS_23") (pintype "input"))
    )
    (net (code "54") (name "/EMI_WEN") (class "Default")
      (node (ref "U1") (pin "77") (pinfunction "EMI_WEN_77") (pintype "output"))
      (node (ref "U2") (pin "21") (pinfunction "#WE_21") (pintype "input"))
    )
    (net (code "55") (name "/GPMI_ALE") (class "Default")
      (node (ref "U1") (pin "20") (pinfunction "GPMI_ALE/LCD_D17_20") (pintype "bidirectional"))
      (node (ref "U3") (pin "17") (pinfunction "ALE_17") (pintype "input"))
    )
    (net (code "56") (name "/GPMI_CE0N") (class "Default")
      (node (ref "R14") (pin "1") (pinfunction "1_1") (pintype "passive"))
      (node (ref "U1") (pin "82") (pinfunction "GPMI_CE0N_82") (pintype "bidirectional"))
      (node (ref "U3") (pin "9") (pinfunction "#CE_9") (pintype "input"))
    )
    (net (code "57") (name "/GPMI_CLE") (class "Default")
      (node (ref "U1") (pin "19") (pinfunction "GPMI_CLE/LCD_D16_19") (pintype "bidirectional"))
      (node (ref "U3") (pin "16") (pinfunction "CLE_16") (pintype "input"))
    )
    (net (code "58") (name "/GPMI_D00") (class "Default")
      (node (ref "U1") (pin "22") (pinfunction "GPMI_D00/LCD_D08/SSP2_DATA0_22") (pintype "bidirectional"))
      (node (ref "U3") (pin "29") (pinfunction "I/O0_29") (pintype "bidirectional"))
    )
    (net (code "59") (name "/GPMI_D01") (class "Default")
      (node (ref "U1") (pin "23") (pinfunction "GPMI_D01/LCD_D09/SSP2_DATA1_23") (pintype "bidirectional"))
      (node (ref "U3") (pin "30") (pinfunction "I/O1_30") (pintype "bidirectional"))
    )
    (net (code "60") (name "/GPMI_D02") (class "Default")
      (node (ref "U1") (pin "24") (pinfunction "GPMI_D02/LCD_D10/SSP2_DATA2_24") (pintype "bidirectional"))
      (node (ref "U3") (pin "31") (pinfunction "I/O2_31") (pintype "bidirectional"))
    )
    (net (code "61") (name "/GPMI_D03") (class "Default")
      (node (ref "U1") (pin "25") (pinfunction "GPMI_D03/LCD_D11/SSP2_DATA3_25") (pintype "bidirectional"))
      (node (ref "U3") (pin "32") (pinfunction "I/O3_32") (pintype "bidirectional"))
    )
    (net (code "62") (name "/GPMI_D04") (class "Default")
      (node (ref "U1") (pin "27") (pinfunction "GPMI_D04/LCD_D12/SSP2_DATA4_27") (pintype "bidirectional"))
      (node (ref "U3") (pin "41") (pinfunction "I/O4_41") (pintype "bidirectional"))
    )
    (net (code "63") (name "/GPMI_D05") (class "Default")
      (node (ref "U1") (pin "26") (pinfunction "GPMI_D05/LCD_D13/SSP2_DATA5_26") (pintype "bidirectional"))
      (node (ref "U3") (pin "42") (pinfunction "I/O5_42") (pintype "bidirectional"))
    )
    (net (code "64") (name "/GPMI_D06") (class "Default")
      (node (ref "U1") (pin "29") (pinfunction "GPMI_D06/LCD_D14/SSP2_DATA6_29") (pintype "bidirectional"))
      (node (ref "U3") (pin "43") (pinfunction "I/O6_43") (pintype "bidirectional"))
    )
    (net (code "65") (name "/GPMI_D07") (class "Default")
      (node (ref "U1") (pin "28") (pinfunction "GPMI_D07/LCD_D15/SSP2_DATA7_28") (pintype "bidirectional"))
      (node (ref "U3") (pin "44") (pinfunction "I/O7_44") (pintype "bidirectional"))
    )
    (net (code "66") (name "/GPMI_RDN") (class "Default")
      (node (ref "U1") (pin "31") (pinfunction "GPMI_RDN_31") (pintype "bidirectional"))
      (node (ref "U3") (pin "8") (pinfunction "#RE_8") (pintype "input"))
    )
    (net (code "67") (name "/GPMI_RDY0") (class "Default")
      (node (ref "R13") (pin "1") (pinfunction "1_1") (pintype "passive"))
      (node (ref "U1") (pin "32") (pinfunction "GPMI_RDY0/SSP2_DETECT_32") (pintype "bidirectional"))
      (node (ref "U3") (pin "7") (pinfunction "R/#B_7") (pintype "output"))
    )
    (net (code "68") (name "/GPMI_WPN") (class "Default")
      (node (ref "R15") (pin "2") (pinfunction "2_2") (pintype "passive"))
      (node (ref "U1") (pin "34") (pinfunction "GPMI_WPN_34") (pintype "bidirectional"))
      (node (ref "U3") (pin "19") (pinfunction "#WP_19") (pintype "input"))
    )
    (net (code "69") (name "/GPMI_WRN") (class "Default")
      (node (ref "U1") (pin "33") (pinfunction "GPMI_WRN/SSP2_SCK_33") (pintype "bidirectional"))
      (node (ref "U3") (pin "18") (pinfunction "#WE_18") (pintype "input"))
    )
    (net (code "70") (name "/HP_VGND") (class "Default")
      (node (ref "U1") (pin "111") (pinfunction "HP_VGND_111") (pintype "power_in"))
    )
    (net (code "71") (name "/I2C_SCL") (class "Default")
      (node (ref "IC1") (pin "6") (pinfunction "SCL_6") (pintype "input"))
      (node (ref "R5") (pin "1") (pinfunction "1_1") (pintype "passive"))
      (node (ref "U1") (pin "11") (pinfunction "LCD_ENABLE/I2C_SCL_11") (pintype "bidirectional"))
    )
    (net (code "72") (name "/I2C_SDA") (class "Default")
      (node (ref "IC1") (pin "5") (pinfunction "SDA_5") (pintype "bidirectional"))
      (node (ref "R6") (pin "2") (pinfunction "2_2") (pintype "passive"))
      (node (ref "U1") (pin "15") (pinfunction "LCD_HSYNC/I2C_SDA_15") (pintype "bidirectional"))
    )
    (net (code "73") (name "/LCD_D00") (class "Default")
      (node (ref "R23") (pin "2") (pinfunction "2_2") (pintype "passive"))
      (node (ref "R27") (pin "2") (pinfunction "2_2") (pintype "passive"))
      (node (ref "U1") (pin "2") (pinfunction "LCD_D00_2") (pintype "bidirectional"))
    )
    (net (code "74") (name "/LCD_D01") (class "Default")
      (node (ref "R22") (pin "2") (pinfunction "2_2") (pintype "passive"))
      (node (ref "R26") (pin "2") (pinfunction "2_2") (pintype "passive"))
      (node (ref "U1") (pin "3") (pinfunction "LCD_D01_3") (pintype "bidirectional"))
    )
    (net (code "75") (name "/LCD_D02") (class "Default")
      (node (ref "R21") (pin "2") (pinfunction "2_2") (pintype "passive"))
      (node (ref "R25") (pin "2") (pinfunction "2_2") (pintype "passive"))
      (node (ref "U1") (pin "4") (pinfunction "LCD_D02_4") (pintype "bidirectional"))
    )
    (net (code "76") (name "/LCD_D03") (class "Default")
      (node (ref "R20") (pin "2") (pinfunction "2_2") (pintype "passive"))
      (node (ref "R24") (pin "2") (pinfunction "2_2") (pintype "passive"))
      (node (ref "U1") (pin "5") (pinfunction "LCD_D03_5") (pintype "bidirectional"))
    )
    (net (code "77") (name "/PSWITCH") (class "Default")
      (node (ref "C5") (pin "1") (pinfunction "1_1") (pintype "passive"))
      (node (ref "R2") (pin "2") (pinfunction "2_2") (pintype "passive"))
      (node (ref "U1") (pin "119") (pinfunction "PSWITCH_119") (pintype "input"))
    )
    (net (code "78") (name "/SSP1_CMD") (class "Default")
      (node (ref "R11") (pin "1") (pinfunction "1_1") (pintype "passive"))
      (node (ref "SD/MMC1") (pin "3") (pinfunction "CMD/DI_3") (pintype "input"))
      (node (ref "U1") (pin "83") (pinfunction "SSP1_CMD/SPI1_MOSI/JTAG_TDO_83") (pintype "bidirectional"))
    )
    (net (code "79") (name "/SSP1_DATA0") (class "Default")
      (node (ref "R10") (pin "1") (pinfunction "1_1") (pintype "passive"))
      (node (ref "SD/MMC1") (pin "7") (pinfunction "DAT0/DO_7") (pintype "output"))
      (node (ref "U1") (pin "84") (pinfunction "SSP1_DATA0/SPI1_MISO/JTAG_TDI_84") (pintype "bidirectional"))
    )
    (net (code "80") (name "/SSP1_DATA1") (class "Default")
      (node (ref "R9") (pin "1") (pinfunction "1_1") (pintype "passive"))
      (node (ref "SD/MMC1") (pin "8") (pinfunction "DAT1/RES_8") (pintype "bidirectional"))
      (node (ref "U1") (pin "85") (pinfunction "SSP1_DATA1/I2C_SCL/JTAG_TCLK_85") (pintype "bidirectional"))
    )
    (net (code "81") (name "/SSP1_DATA2") (class "Default")
      (node (ref "R8") (pin "1") (pinfunction "1_1") (pintype "passive"))
      (node (ref "SD/MMC1") (pin "1") (pinfunction "DAT2/RES_1") (pintype "bidirectional"))
      (node (ref "U1") (pin "86") (pinfunction "SSP1_DATA2/I2C_SDA/JTAG_RTCK_86") (pintype "bidirectional"))
    )
    (net (code "82") (name "/SSP1_DATA3") (class "Default")
      (node (ref "R12") (pin "2") (pinfunction "2_2") (pintype "passive"))
      (node (ref "SD/MMC1") (pin "2") (pinfunction "CD/DAT3/CS_2") (pintype "input"))
      (node (ref "U1") (pin "87") (pinfunction "SSP1_DATA3/SPI1_SS#/JTAG_TMS_87") (pintype "bidirectional"))
    )
    (net (code "83") (name "/SSP1_SCK") (class "Default")
      (node (ref "SD/MMC1") (pin "5") (pinfunction "CLK/SCLK_5") (pintype "input"))
      (node (ref "U1") (pin "90") (pinfunction "SSP1_SCK/SPI1_SCK/JTAG_TRST_90") (pintype "bidirectional"))
    )
    (net (code "84") (name "/USB_DM") (class "Default")
      (node (ref "U1") (pin "123") (pinfunction "USB_DM_123") (pintype "bidirectional"))
      (node (ref "X1") (pin "2") (pinfunction "2_2") (pintype "passive"))
    )
    (net (code "85") (name "/USB_DP") (class "Default")
      (node (ref "U1") (pin "124") (pinfunction "USB_DP_124") (pintype "bidirectional"))
      (node (ref "X1") (pin "3") (pinfunction "3_3") (pintype "passive"))
    )
    (net (code "86") (name "/VDD4P2") (class "Default")
      (node (ref "C16") (pin "1") (pinfunction "1_1") (pintype "passive"))
      (node (ref "C17") (pin "1") (pinfunction "1_1") (pintype "passive"))
      (node (ref "D1") (pin "C") (pinfunction "C_C") (pintype "passive"))
      (node (ref "U1") (pin "101") (pinfunction "VDD4P2_101") (pintype "power_in"))
    )
    (net (code "87") (name "/VDDIO_DRAM") (class "Default")
      (node (ref "C13") (pin "1") (pinfunction "1_1") (pintype "passive"))
      (node (ref "C14") (pin "1") (pinfunction "1_1") (pintype "passive"))
      (node (ref "C44") (pin "2") (pinfunction "2_2") (pintype "passive"))
      (node (ref "C45") (pin "2") (pinfunction "2_2") (pintype "passive"))
      (node (ref "C46") (pin "2") (pinfunction "2_2") (pintype "passive"))
      (node (ref "C47") (pin "2") (pinfunction "2_2") (pintype "passive"))
      (node (ref "C48") (pin "2") (pinfunction "2_2") (pintype "passive"))
      (node (ref "C49") (pin "2") (pinfunction "2_2") (pintype "passive"))
      (node (ref "C50") (pin "2") (pinfunction "2_2") (pintype "passive"))
      (node (ref "C51") (pin "2") (pinfunction "2_2") (pintype "passive"))
      (node (ref "C52") (pin "2") (pinfunction "2_2") (pintype "passive"))
      (node (ref "R17") (pin "2") (pinfunction "2_2") (pintype "passive"))
      (node (ref "R18") (pin "2") (pinfunction "2_2") (pintype "passive"))
      (node (ref "U1") (pin "38") (pinfunction "VDDIO_EMIQ_38") (pintype "power_in"))
      (node (ref "U1") (pin "45") (pinfunction "VDDIO_EMI1_45") (pintype "power_in"))
      (node (ref "U1") (pin "53") (pinfunction "VDDIO_EMI2_53") (pintype "power_in"))
      (node (ref "U2") (pin "1") (pinfunction "VDD1_1") (pintype "power_in"))
      (node (ref "U2") (pin "15") (pinfunction "VDDQ3_15") (pintype "power_in"))
      (node (ref "U2") (pin "18") (pinfunction "VDD2_18") (pintype "power_in"))
      (node (ref "U2") (pin "3") (pinfunction "VDDQ1_3") (pintype "power_in"))
      (node (ref "U2") (pin "33") (pinfunction "VDD3_33") (pintype "power_in"))
      (node (ref "U2") (pin "55") (pinfunction "VDDQ4_55") (pintype "power_in"))
      (node (ref "U2") (pin "61") (pinfunction "VDDQ5_61") (pintype "power_in"))
      (node (ref "U2") (pin "9") (pinfunction "VDDQ2_9") (pintype "power_in"))
    )
    (net (code "88") (name "/VDDM{slash}LRADC4") (class "Default")
      (node (ref "C15") (pin "1") (pinfunction "1_1") (pintype "passive"))
      (node (ref "U1") (pin "106") (pinfunction "VDDM/LRADC4_106") (pintype "power_in"))
    )
    (net (code "89") (name "/VDDXTAL") (class "Default")
      (node (ref "C34") (pin "1") (pinfunction "1_1") (pintype "passive"))
      (node (ref "S1") (pin "3") (pinfunction "P_3") (pintype "passive"))
      (node (ref "S1") (pin "4") (pinfunction "P1_4") (pintype "passive"))
      (node (ref "U1") (pin "120") (pinfunction "VDDXTAL_120") (pintype "passive"))
    )
    (net (code "90") (name "/XTALI") (class "Default")
      (node (ref "C35") (pin "2") (pinfunction "2_2") (pintype "passive"))
      (node (ref "Q1") (pin "2") (pinfunction "2_2") (pintype "passive"))
      (node (ref "T1") (pin "3") (pinfunction "C_3") (pintype "passive"))
      (node (ref "U1") (pin "122") (pinfunction "XTALI_122") (pintype "input"))
    )
    (net (code "91") (name "/XTALO") (class "Default")
      (node (ref "C36") (pin "2") (pinfunction "2_2") (pintype "passive"))
      (node (ref "Q1") (pin "1") (pinfunction "1_1") (pintype "passive"))
      (node (ref "T2") (pin "3") (pinfunction "C_3") (pintype "passive"))
      (node (ref "U1") (pin "121") (pinfunction "XTALO_121") (pintype "output"))
    )
    (net (code "92") (name "GND") (class "Default")
      (node (ref "C1") (pin "2") (pinfunction "2_2") (pintype "passive"))
      (node (ref "C10") (pin "2") (pinfunction "2_2") (pintype "passive"))
      (node (ref "C11") (pin "2") (pinfunction "2_2") (pintype "passive"))
      (node (ref "C12") (pin "2") (pinfunction "2_2") (pintype "passive"))
      (node (ref "C13") (pin "2") (pinfunction "2_2") (pintype "passive"))
      (node (ref "C14") (pin "2") (pinfunction "2_2") (pintype "passive"))
      (node (ref "C15") (pin "2") (pinfunction "2_2") (pintype "passive"))
      (node (ref "C16") (pin "2") (pinfunction "2_2") (pintype "passive"))
      (node (ref "C17") (pin "2") (pinfunction "2_2") (pintype "passive"))
      (node (ref "C18") (pin "2") (pinfunction "2_2") (pintype "passive"))
      (node (ref "C19") (pin "2") (pinfunction "2_2") (pintype "passive"))
      (node (ref "C2") (pin "2") (pinfunction "2_2") (pintype "passive"))
      (node (ref "C20") (pin "2") (pinfunction "2_2") (pintype "passive"))
      (node (ref "C21") (pin "2") (pinfunction "2_2") (pintype "passive"))
      (node (ref "C22") (pin "2") (pinfunction "2_2") (pintype "passive"))
      (node (ref "C23") (pin "2") (pinfunction "2_2") (pintype "passive"))
      (node (ref "C24") (pin "2") (pinfunction "2_2") (pintype "passive"))
      (node (ref "C25") (pin "2") (pinfunction "2_2") (pintype "passive"))
      (node (ref "C26") (pin "2") (pinfunction "2_2") (pintype "passive"))
      (node (ref "C27") (pin "2") (pinfunction "2_2") (pintype "passive"))
      (node (ref "C28") (pin "2") (pinfunction "2_2") (pintype "passive"))
      (node (ref "C29") (pin "2") (pinfunction "2_2") (pintype "passive"))
      (node (ref "C3") (pin "-") (pinfunction "-_-") (pintype "passive"))
      (node (ref "C30") (pin "2") (pinfunction "2_2") (pintype "passive"))
      (node (ref "C31") (pin "2") (pinfunction "2_2") (pintype "passive"))
      (node (ref "C32") (pin "2") (pinfunction "2_2") (pintype "passive"))
      (node (ref "C33") (pin "2") (pinfunction "2_2") (pintype "passive"))
      (node (ref "C34") (pin "2") (pinfunction "2_2") (pintype "passive"))
      (node (ref "C35") (pin "1") (pinfunction "1_1") (pintype "passive"))
      (node (ref "C36") (pin "1") (pinfunction "1_1") (pintype "passive"))
      (node (ref "C37") (pin "2") (pinfunction "2_2") (pintype "passive"))
      (node (ref "C38") (pin "2") (pinfunction "2_2") (pintype "passive"))
      (node (ref "C39") (pin "1") (pinfunction "1_1") (pintype "passive"))
      (node (ref "C4") (pin "-") (pinfunction "-_-") (pintype "passive"))
      (node (ref "C40") (pin "1") (pinfunction "1_1") (pintype "passive"))
      (node (ref "C41") (pin "1") (pinfunction "1_1") (pintype "passive"))
      (node (ref "C42") (pin "1") (pinfunction "1_1") (pintype "passive"))
      (node (ref "C43") (pin "1") (pinfunction "1_1") (pintype "passive"))
      (node (ref "C44") (pin "1") (pinfunction "1_1") (pintype "passive"))
      (node (ref "C45") (pin "1") (pinfunction "1_1") (pintype "passive"))
      (node (ref "C46") (pin "1") (pinfunction "1_1") (pintype "passive"))
      (node (ref "C47") (pin "1") (pinfunction "1_1") (pintype "passive"))
      (node (ref "C48") (pin "1") (pinfunction "1_1") (pintype "passive"))
      (node (ref "C49") (pin "1") (pinfunction "1_1") (pintype "passive"))
      (node (ref "C5") (pin "2") (pinfunction "2_2") (pintype "passive"))
      (node (ref "C50") (pin "1") (pinfunction "1_1") (pintype "passive"))
      (node (ref "C51") (pin "1") (pinfunction "1_1") (pintype "passive"))
      (node (ref "C53") (pin "1") (pinfunction "1_1") (pintype "passive"))
      (node (ref "C6") (pin "2") (pinfunction "2_2") (pintype "passive"))
      (node (ref "C7") (pin "2") (pinfunction "2_2") (pintype "passive"))
      (node (ref "C9") (pin "2") (pinfunction "2_2") (pintype "passive"))
      (node (ref "IC1") (pin "1") (pinfunction "A0_1") (pintype "input"))
      (node (ref "IC1") (pin "2") (pinfunction "A1_2") (pintype "input"))
      (node (ref "IC1") (pin "3") (pinfunction "A2_3") (pintype "input"))
      (node (ref "IC1") (pin "4") (pinfunction "GND_4") (pintype "power_in"))
      (node (ref "IC1") (pin "7") (pinfunction "WP_7") (pintype "input"))
      (node (ref "J1") (pin "1") (pinfunction "1_1") (pintype "passive"))
      (node (ref "J1") (pin "2") (pinfunction "2_2") (pintype "passive"))
      (node (ref "JP1") (pin "5") (pinfunction "5_5") (pintype "passive"))
      (node (ref "R1") (pin "2") (pinfunction "2_2") (pintype "passive"))
      (node (ref "R12") (pin "1") (pinfunction "1_1") (pintype "passive"))
      (node (ref "R15") (pin "1") (pinfunction "1_1") (pintype "passive"))
      (node (ref "R16") (pin "1") (pinfunction "1_1") (pintype "passive"))
      (node (ref "R24") (pin "1") (pinfunction "1_1") (pintype "passive"))
      (node (ref "R25") (pin "1") (pinfunction "1_1") (pintype "passive"))
      (node (ref "R26") (pin "1") (pinfunction "1_1") (pintype "passive"))
      (node (ref "R27") (pin "1") (pinfunction "1_1") (pintype "passive"))
      (node (ref "R4") (pin "1") (pinfunction "1_1") (pintype "passive"))
      (node (ref "R7") (pin "1") (pinfunction "1_1") (pintype "passive"))
      (node (ref "SD/MMC1") (pin "6") (pinfunction "VSS_6") (pintype "power_in"))
      (node (ref "T1") (pin "2") (pinfunction "E_2") (pintype "passive"))
      (node (ref "T2") (pin "1") (pinfunction "B_1") (pintype "passive"))
      (node (ref "T2") (pin "2") (pinfunction "E_2") (pintype "passive"))
      (node (ref "U$1") (pin "4") (pinfunction "GND_4") (pintype "passive"))
      (node (ref "U1") (pin "105") (pinfunction "VSSA4_105") (pintype "power_in"))
      (node (ref "U1") (pin "112") (pinfunction "VSSA1_112") (pintype "power_in"))
      (node (ref "U1") (pin "118") (pinfunction "VSSA2_118") (pintype "power_in"))
      (node (ref "U1") (pin "30") (pinfunction "VSSD1_30") (pintype "power_in"))
      (node (ref "U1") (pin "35") (pinfunction "VSSD2_35") (pintype "power_in"))
      (node (ref "U1") (pin "98") (pinfunction "DCDC_GND_98") (pintype "power_in"))
      (node (ref "U2") (pin "12") (pinfunction "VSSQ2_12") (pintype "power_in"))
      (node (ref "U2") (pin "34") (pinfunction "VSS1_34") (pintype "power_in"))
      (node (ref "U2") (pin "48") (pinfunction "VSS2_48") (pintype "power_in"))
      (node (ref "U2") (pin "52") (pinfunction "VSSQ3_52") (pintype "power_in"))
      (node (ref "U2") (pin "58") (pinfunction "VSSQ4_58") (pintype "power_in"))
      (node (ref "U2") (pin "6") (pinfunction "VSSQ1_6") (pintype "power_in"))
      (node (ref "U2") (pin "64") (pinfunction "VSSQ5_64") (pintype "power_in"))
      (node (ref "U2") (pin "66") (pinfunction "VSS3_66") (pintype "power_in"))
      (node (ref "U3") (pin "13") (pinfunction "VSS_13") (pintype "power_in"))
      (node (ref "U3") (pin "36") (pinfunction "VSS_36") (pintype "power_in"))
      (node (ref "X1") (pin "4") (pinfunction "4_4") (pintype "passive"))
      (node (ref "X1") (pin "S1") (pinfunction "S1_S1") (pintype "passive"))
      (node (ref "X1") (pin "S2") (pinfunction "S2_S2") (pintype "passive"))
    )
    (net (code "93") (name "Net-(R20-Pad1)") (class "Default")
      (node (ref "R20") (pin "1") (pinfunction "1_1") (pintype "passive"))
      (node (ref "SW1") (pin "1") (pinfunction "1_1") (pintype "passive"))
    )
    (net (code "94") (name "Net-(R21-Pad1)") (class "Default")
      (node (ref "R21") (pin "1") (pinfunction "1_1") (pintype "passive"))
      (node (ref "SW1") (pin "2") (pinfunction "2_2") (pintype "passive"))
    )
    (net (code "95") (name "Net-(R22-Pad1)") (class "Default")
      (node (ref "R22") (pin "1") (pinfunction "1_1") (pintype "passive"))
      (node (ref "SW1") (pin "3") (pinfunction "3_3") (pintype "passive"))
    )
    (net (code "96") (name "Net-(R23-Pad1)") (class "Default")
      (node (ref "R23") (pin "1") (pinfunction "1_1") (pintype "passive"))
      (node (ref "SW1") (pin "4") (pinfunction "4_4") (pintype "passive"))
    )
    (net (code "97") (name "Net-(S1-S)") (class "Default")
      (node (ref "R1") (pin "1") (pinfunction "1_1") (pintype "passive"))
      (node (ref "R2") (pin "1") (pinfunction "1_1") (pintype "passive"))
      (node (ref "S1") (pin "1") (pinfunction "S_1") (pintype "passive"))
      (node (ref "S1") (pin "2") (pinfunction "S1_2") (pintype "passive"))
    )
    (net (code "98") (name "Net-(S2-S)") (class "Default")
      (node (ref "R3") (pin "1") (pinfunction "1_1") (pintype "passive"))
      (node (ref "S2") (pin "1") (pinfunction "S_1") (pintype "passive"))
      (node (ref "S2") (pin "2") (pinfunction "S1_2") (pintype "passive"))
    )
    (net (code "99") (name "Net-(SD/MMC1-VDD)") (class "Default")
      (node (ref "C40") (pin "2") (pinfunction "2_2") (pintype "passive"))
      (node (ref "C41") (pin "2") (pinfunction "2_2") (pintype "passive"))
      (node (ref "L3") (pin "2") (pinfunction "2_2") (pintype "passive"))
      (node (ref "SD/MMC1") (pin "4") (pinfunction "VDD_4") (pintype "power_in"))
    )
    (net (code "100") (name "Net-(T1-B)") (class "Default")
      (node (ref "C6") (pin "1") (pinfunction "1_1") (pintype "passive"))
      (node (ref "R3") (pin "2") (pinfunction "2_2") (pintype "passive"))
      (node (ref "R4") (pin "2") (pinfunction "2_2") (pintype "passive"))
      (node (ref "T1") (pin "1") (pinfunction "B_1") (pintype "passive"))
    )
    (net (code "101") (name "Net-(U$1-VI)") (class "Default")
      (node (ref "C1") (pin "1") (pinfunction "1_1") (pintype "passive"))
      (node (ref "J1") (pin "3") (pinfunction "3_3") (pintype "passive"))
      (node (ref "U$1") (pin "1") (pinfunction "VI_1") (pintype "input"))
    )
    (net (code "102") (name "Net-(U1-DCDC_LN1)") (class "Default")
      (node (ref "L2") (pin "2") (pinfunction "2_2") (pintype "passive"))
      (node (ref "U1") (pin "97") (pinfunction "DCDC_LN1_97") (pintype "passive"))
    )
    (net (code "103") (name "Net-(U1-DCDC_LP)") (class "Default")
      (node (ref "L2") (pin "1") (pinfunction "1_1") (pintype "passive"))
      (node (ref "U1") (pin "99") (pinfunction "DCDC_LP_99") (pintype "passive"))
    )
    (net (code "104") (name "Net-(U1-LCD_RS)") (class "Default")
      (node (ref "R19") (pin "1") (pinfunction "1_1") (pintype "passive"))
      (node (ref "U1") (pin "14") (pinfunction "LCD_RS_14") (pintype "bidirectional"))
    )
    (net (code "105") (name "Net-(U1-VAG)") (class "Default")
      (node (ref "C39") (pin "2") (pinfunction "2_2") (pintype "passive"))
      (node (ref "U1") (pin "117") (pinfunction "VAG_117") (pintype "passive"))
    )
    (net (code "106") (name "Net-(U2-VREF)") (class "Default")
      (node (ref "C52") (pin "1") (pinfunction "1_1") (pintype "passive"))
      (node (ref "C53") (pin "2") (pinfunction "2_2") (pintype "passive"))
      (node (ref "R16") (pin "2") (pinfunction "2_2") (pintype "passive"))
      (node (ref "R17") (pin "1") (pinfunction "1_1") (pintype "passive"))
      (node (ref "U2") (pin "49") (pinfunction "VREF_49") (pintype "input"))
    )
    (net (code "107") (name "unconnected-(SD/MMC1-CP_E-Pad9)") (class "Default")
      (node (ref "SD/MMC1") (pin "9") (pinfunction "CP_E_9") (pintype "input"))
    )
    (net (code "108") (name "unconnected-(SD/MMC1-PACK1-Pad10)") (class "Default")
      (node (ref "SD/MMC1") (pin "10") (pinfunction "PACK1_10") (pintype "input"))
    )
    (net (code "109") (name "unconnected-(U1-GPMI_CE1N-Pad81)") (class "Default")
      (node (ref "U1") (pin "81") (pinfunction "GPMI_CE1N_81") (pintype "bidirectional"))
    )
    (net (code "110") (name "unconnected-(U1-GPMI_RDY1{slash}SSP2_CMD-Pad21)") (class "Default")
      (node (ref "U1") (pin "21") (pinfunction "GPMI_RDY1/SSP2_CMD_21") (pintype "bidirectional"))
    )
    (net (code "111") (name "unconnected-(U1-HPL-Pad113)") (class "Default")
      (node (ref "U1") (pin "113") (pinfunction "HPL_113") (pintype "output"))
    )
    (net (code "112") (name "unconnected-(U1-HPR-Pad109)") (class "Default")
      (node (ref "U1") (pin "109") (pinfunction "HPR_109") (pintype "output"))
    )
    (net (code "113") (name "unconnected-(U1-LCD_CS-Pad10)") (class "Default")
      (node (ref "U1") (pin "10") (pinfunction "LCD_CS_10") (pintype "bidirectional"))
    )
    (net (code "114") (name "unconnected-(U1-LCD_D04-Pad6)") (class "Default")
      (node (ref "U1") (pin "6") (pinfunction "LCD_D04_6") (pintype "bidirectional"))
    )
    (net (code "115") (name "unconnected-(U1-LCD_D05-Pad7)") (class "Default")
      (node (ref "U1") (pin "7") (pinfunction "LCD_D05_7") (pintype "bidirectional"))
    )
    (net (code "116") (name "unconnected-(U1-LCD_D06-Pad8)") (class "Default")
      (node (ref "U1") (pin "8") (pinfunction "LCD_D06_8") (pintype "bidirectional"))
    )
    (net (code "117") (name "unconnected-(U1-LCD_D07-Pad9)") (class "Default")
      (node (ref "U1") (pin "9") (pinfunction "LCD_D07_9") (pintype "bidirectional"))
    )
    (net (code "118") (name "unconnected-(U1-LCD_DOTCK{slash}GPMI_RDY3-Pad17)") (class "Default")
      (node (ref "U1") (pin "17") (pinfunction "LCD_DOTCK/GPMI_RDY3_17") (pintype "bidirectional"))
    )
    (net (code "119") (name "unconnected-(U1-LCD_RESET{slash}GPMI_CE3N-Pad12)") (class "Default")
      (node (ref "U1") (pin "12") (pinfunction "LCD_RESET/GPMI_CE3N_12") (pintype "bidirectional"))
    )
    (net (code "120") (name "unconnected-(U1-LCD_VSYNC{slash}LCD_BUSY-Pad16)") (class "Default")
      (node (ref "U1") (pin "16") (pinfunction "LCD_VSYNC/LCD_BUSY_16") (pintype "bidirectional"))
    )
    (net (code "121") (name "unconnected-(U1-LCD_WR-Pad13)") (class "Default")
      (node (ref "U1") (pin "13") (pinfunction "LCD_WR_13") (pintype "bidirectional"))
    )
    (net (code "122") (name "unconnected-(U1-LINE1_INL-Pad115)") (class "Default")
      (node (ref "U1") (pin "115") (pinfunction "LINE1_INL_115") (pintype "input"))
    )
    (net (code "123") (name "unconnected-(U1-LINE1_INR-Pad114)") (class "Default")
      (node (ref "U1") (pin "114") (pinfunction "LINE1_INR_114") (pintype "input"))
    )
    (net (code "124") (name "unconnected-(U1-LRADC0-Pad108)") (class "Default")
      (node (ref "U1") (pin "108") (pinfunction "LRADC0_108") (pintype "bidirectional"))
    )
    (net (code "125") (name "unconnected-(U1-LRADC1-Pad107)") (class "Default")
      (node (ref "U1") (pin "107") (pinfunction "LRADC1_107") (pintype "bidirectional"))
    )
    (net (code "126") (name "unconnected-(U1-MIC-Pad116)") (class "Default")
      (node (ref "U1") (pin "116") (pinfunction "MIC_116") (pintype "input"))
    )
    (net (code "127") (name "unconnected-(U1-PWM2{slash}GPMI_RDY3-Pad91)") (class "Default")
      (node (ref "U1") (pin "91") (pinfunction "PWM2/GPMI_RDY3_91") (pintype "bidirectional"))
    )
    (net (code "128") (name "unconnected-(U1-SSP1_DETECT{slash}GPMI_CE3N{slash}USB_ID-Pad88)") (class "Default")
      (node (ref "U1") (pin "88") (pinfunction "SSP1_DETECT/GPMI_CE3N/USB_ID_88") (pintype "bidirectional"))
    )
    (net (code "129") (name "unconnected-(U1-VDAC1-Pad104)") (class "Default")
      (node (ref "U1") (pin "104") (pinfunction "VDAC1_104") (pintype "output"))
    )
    (net (code "130") (name "unconnected-(U2-NC1-Pad14)") (class "Default")
      (node (ref "U2") (pin "14") (pinfunction "NC1_14") (pintype "no_connect"))
    )
    (net (code "131") (name "unconnected-(U2-NC2-Pad17)") (class "Default")
      (node (ref "U2") (pin "17") (pinfunction "NC2_17") (pintype "no_connect"))
    )
    (net (code "132") (name "unconnected-(U2-NC3-Pad19)") (class "Default")
      (node (ref "U2") (pin "19") (pinfunction "NC3_19") (pintype "no_connect"))
    )
    (net (code "133") (name "unconnected-(U2-NC4-Pad25)") (class "Default")
      (node (ref "U2") (pin "25") (pinfunction "NC4_25") (pintype "no_connect"))
    )
    (net (code "134") (name "unconnected-(U2-NC5-Pad43)") (class "Default")
      (node (ref "U2") (pin "43") (pinfunction "NC5_43") (pintype "no_connect"))
    )
    (net (code "135") (name "unconnected-(U2-NC6-Pad50)") (class "Default")
      (node (ref "U2") (pin "50") (pinfunction "NC6_50") (pintype "no_connect"))
    )
    (net (code "136") (name "unconnected-(U2-NC7-Pad53)") (class "Default")
      (node (ref "U2") (pin "53") (pinfunction "NC7_53") (pintype "no_connect"))
    )
    (net (code "137") (name "unconnected-(U3-NC-Pad1)") (class "Default")
      (node (ref "U3") (pin "1") (pinfunction "NC_1") (pintype "no_connect"))
    )
    (net (code "138") (name "unconnected-(U3-NC-Pad2)") (class "Default")
      (node (ref "U3") (pin "2") (pinfunction "NC_2") (pintype "no_connect"))
    )
    (net (code "139") (name "unconnected-(U3-NC-Pad3)") (class "Default")
      (node (ref "U3") (pin "3") (pinfunction "NC_3") (pintype "no_connect"))
    )
    (net (code "140") (name "unconnected-(U3-NC-Pad4)") (class "Default")
      (node (ref "U3") (pin "4") (pinfunction "NC_4") (pintype "no_connect"))
    )
    (net (code "141") (name "unconnected-(U3-NC-Pad5)") (class "Default")
      (node (ref "U3") (pin "5") (pinfunction "NC_5") (pintype "no_connect"))
    )
    (net (code "142") (name "unconnected-(U3-NC-Pad6)") (class "Default")
      (node (ref "U3") (pin "6") (pinfunction "NC_6") (pintype "no_connect"))
    )
    (net (code "143") (name "unconnected-(U3-NC-Pad10)") (class "Default")
      (node (ref "U3") (pin "10") (pinfunction "NC_10") (pintype "no_connect"))
    )
    (net (code "144") (name "unconnected-(U3-NC-Pad11)") (class "Default")
      (node (ref "U3") (pin "11") (pinfunction "NC_11") (pintype "no_connect"))
    )
    (net (code "145") (name "unconnected-(U3-NC-Pad14)") (class "Default")
      (node (ref "U3") (pin "14") (pinfunction "NC_14") (pintype "no_connect"))
    )
    (net (code "146") (name "unconnected-(U3-NC-Pad15)") (class "Default")
      (node (ref "U3") (pin "15") (pinfunction "NC_15") (pintype "no_connect"))
    )
    (net (code "147") (name "unconnected-(U3-NC-Pad20)") (class "Default")
      (node (ref "U3") (pin "20") (pinfunction "NC_20") (pintype "no_connect"))
    )
    (net (code "148") (name "unconnected-(U3-NC-Pad21)") (class "Default")
      (node (ref "U3") (pin "21") (pinfunction "NC_21") (pintype "no_connect"))
    )
    (net (code "149") (name "unconnected-(U3-NC-Pad22)") (class "Default")
      (node (ref "U3") (pin "22") (pinfunction "NC_22") (pintype "no_connect"))
    )
    (net (code "150") (name "unconnected-(U3-NC-Pad23)") (class "Default")
      (node (ref "U3") (pin "23") (pinfunction "NC_23") (pintype "no_connect"))
    )
    (net (code "151") (name "unconnected-(U3-NC-Pad24)") (class "Default")
      (node (ref "U3") (pin "24") (pinfunction "NC_24") (pintype "no_connect"))
    )
    (net (code "152") (name "unconnected-(U3-NC-Pad25)") (class "Default")
      (node (ref "U3") (pin "25") (pinfunction "NC_25") (pintype "no_connect"))
    )
    (net (code "153") (name "unconnected-(U3-NC-Pad26)") (class "Default")
      (node (ref "U3") (pin "26") (pinfunction "NC_26") (pintype "no_connect"))
    )
    (net (code "154") (name "unconnected-(U3-NC-Pad27)") (class "Default")
      (node (ref "U3") (pin "27") (pinfunction "NC_27") (pintype "no_connect"))
    )
    (net (code "155") (name "unconnected-(U3-NC-Pad28)") (class "Default")
      (node (ref "U3") (pin "28") (pinfunction "NC_28") (pintype "no_connect"))
    )
    (net (code "156") (name "unconnected-(U3-NC-Pad33)") (class "Default")
      (node (ref "U3") (pin "33") (pinfunction "NC_33") (pintype "no_connect"))
    )
    (net (code "157") (name "unconnected-(U3-NC-Pad34)") (class "Default")
      (node (ref "U3") (pin "34") (pinfunction "NC_34") (pintype "no_connect"))
    )
    (net (code "158") (name "unconnected-(U3-NC-Pad35)") (class "Default")
      (node (ref "U3") (pin "35") (pinfunction "NC_35") (pintype "no_connect"))
    )
    (net (code "159") (name "unconnected-(U3-NC-Pad38)") (class "Default")
      (node (ref "U3") (pin "38") (pinfunction "NC_38") (pintype "no_connect"))
    )
    (net (code "160") (name "unconnected-(U3-NC-Pad39)") (class "Default")
      (node (ref "U3") (pin "39") (pinfunction "NC_39") (pintype "no_connect"))
    )
    (net (code "161") (name "unconnected-(U3-NC-Pad40)") (class "Default")
      (node (ref "U3") (pin "40") (pinfunction "NC_40") (pintype "no_connect"))
    )
    (net (code "162") (name "unconnected-(U3-NC-Pad45)") (class "Default")
      (node (ref "U3") (pin "45") (pinfunction "NC_45") (pintype "no_connect"))
    )
    (net (code "163") (name "unconnected-(U3-NC-Pad46)") (class "Default")
      (node (ref "U3") (pin "46") (pinfunction "NC_46") (pintype "no_connect"))
    )
    (net (code "164") (name "unconnected-(U3-NC-Pad47)") (class "Default")
      (node (ref "U3") (pin "47") (pinfunction "NC_47") (pintype "no_connect"))
    )
    (net (code "165") (name "unconnected-(U3-NC-Pad48)") (class "Default")
      (node (ref "U3") (pin "48") (pinfunction "NC_48") (pintype "no_connect"))
    )
  )
)
